# AP4BP-module-breakout_rev_a-v7.net
KiCad netlist of a schematic drawn in EAGLE
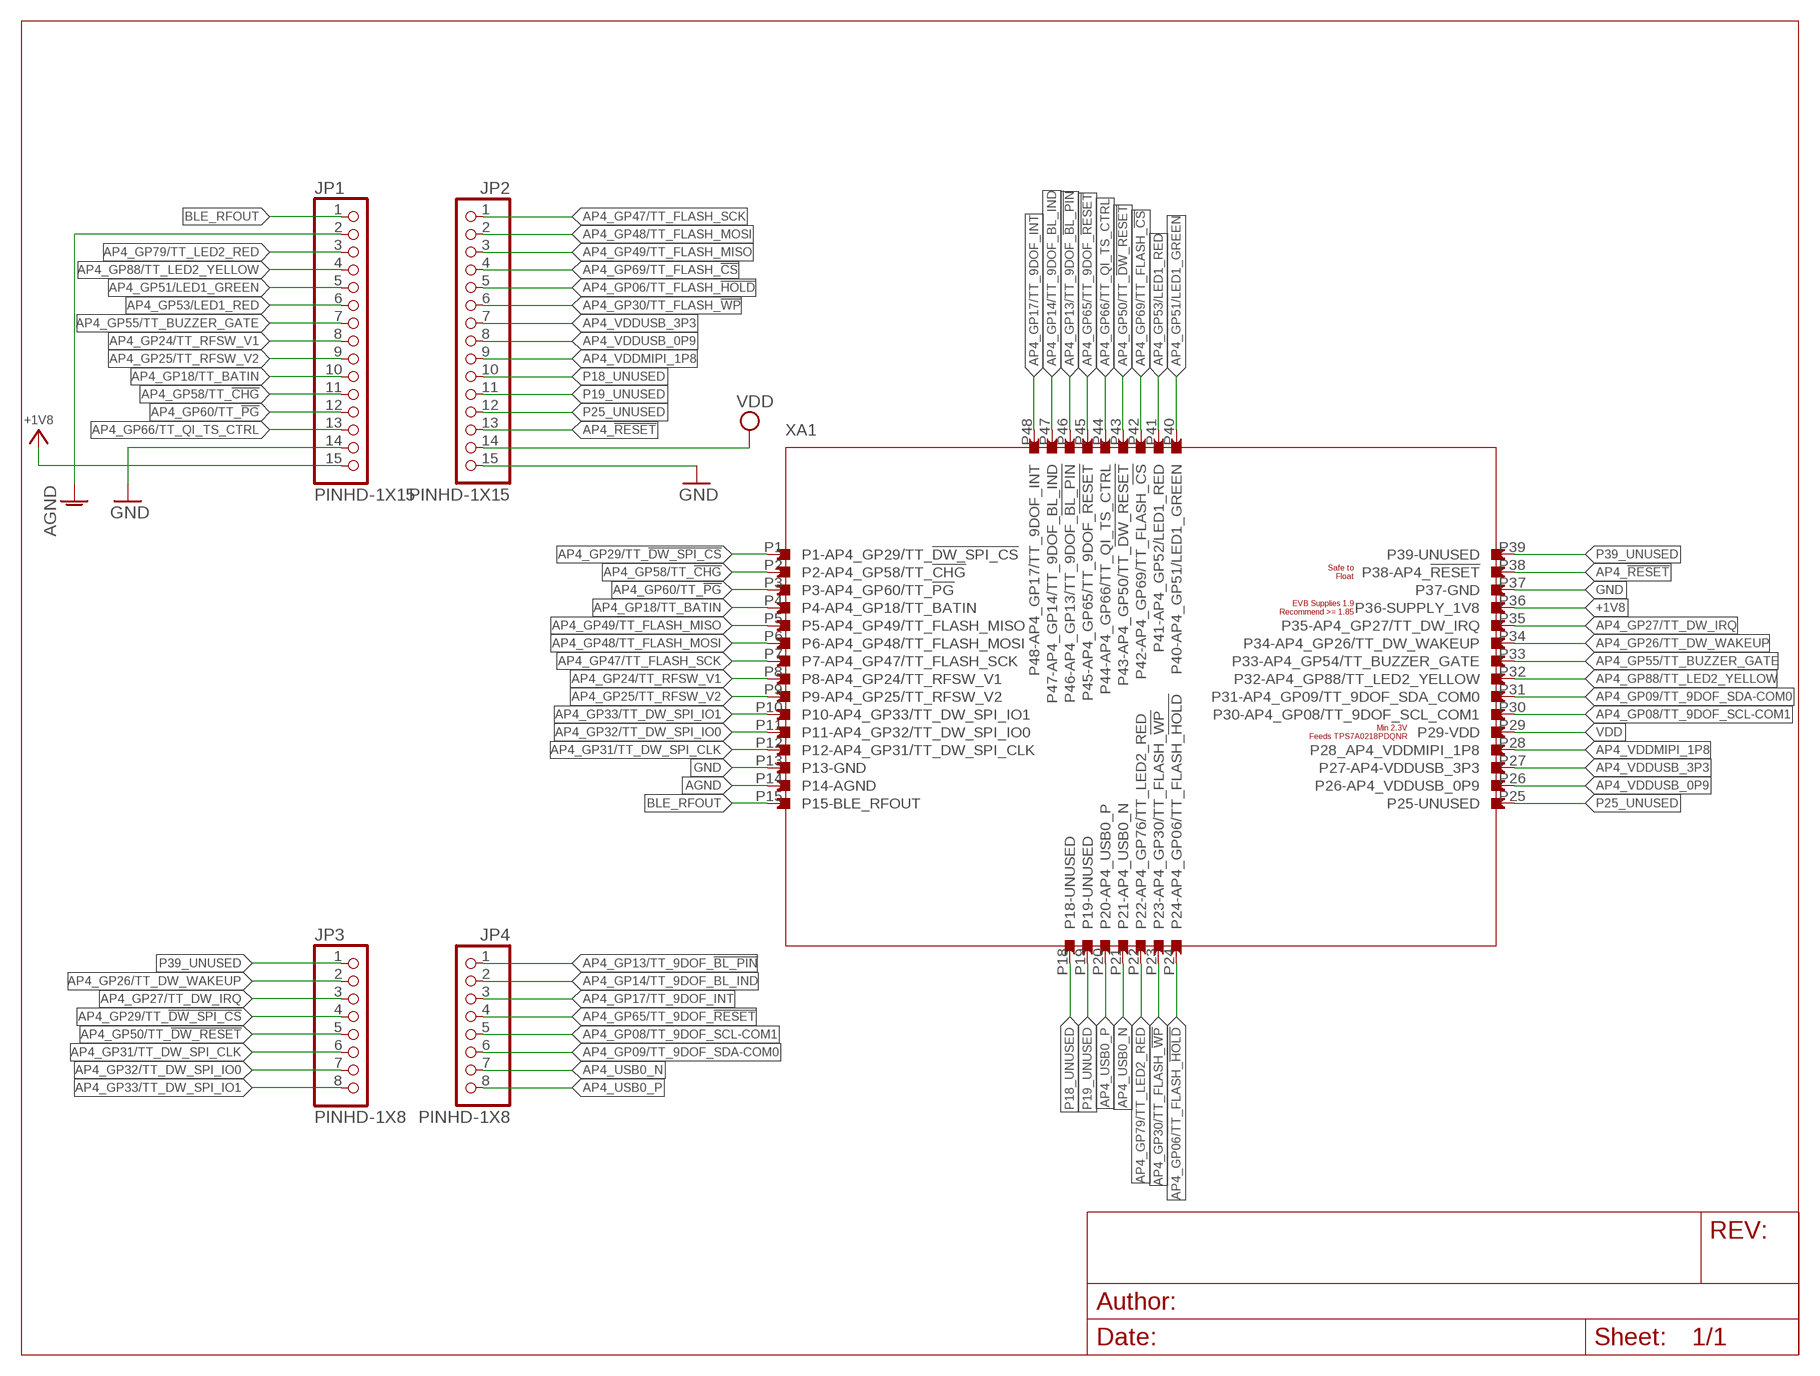
[diagram p0: schematic, sheet 1]

(export (version "E")
  (design (tool "Eeschema 10.0.6"))
  (components
    (comp (ref "JP1")
      (value "PINHD-1X15")
      (footprint "eagle-import:1X15")
      (fields (field (name "MANUFACTURER") "Generic"))
      (libsource (lib "eagle-import") (part "Connector_16378166_PINHD-1X15"))
    )
    (comp (ref "JP2")
      (value "PINHD-1X15")
      (footprint "eagle-import:1X15")
      (libsource (lib "eagle-import") (part "PINHD-1X15"))
    )
    (comp (ref "JP3")
      (value "PINHD-1X8")
      (footprint "eagle-import:1X08")
      (libsource (lib "eagle-import") (part "PINHD-1X8"))
    )
    (comp (ref "JP4")
      (value "PINHD-1X8")
      (footprint "eagle-import:1X08")
      (libsource (lib "eagle-import") (part "PINHD-1X8"))
    )
    (comp (ref "XA1")
      (value "APOLLO4_BLUEPLUS_MODULE")
      (footprint "eagle-import:APOLLO4_BLUEPLUS_MODULE")
      (libsource (lib "eagle-import") (part "APOLLO4_BLUEPLUS_MODULE"))
    )
  )
  (nets
    (net (code "1") (name "+1V8") (class "Default")
      (node (ref "JP1") (pin "15") (pinfunction "15_15") (pintype "passive"))
      (node (ref "XA1") (pin "P36") (pinfunction "P36-SUPPLY_1V8_P36") (pintype "bidirectional"))
    )
    (net (code "2") (name "/AP4_GP06{slash}TT_FLASH_~{HOLD}") (class "Default")
      (node (ref "JP2") (pin "5") (pinfunction "5_5") (pintype "passive"))
      (node (ref "XA1") (pin "P24") (pinfunction "P24-AP4_GP06/TT_FLASH_~{HOLD}_P24") (pintype "bidirectional"))
    )
    (net (code "3") (name "/AP4_GP13{slash}TT_9DOF_~{BL_PIN}") (class "Default")
      (node (ref "JP4") (pin "1") (pinfunction "1_1") (pintype "passive"))
      (node (ref "XA1") (pin "P46") (pinfunction "P46-AP4_GP13/TT_9DOF_~{BL_PIN}_P46") (pintype "bidirectional"))
    )
    (net (code "4") (name "/AP4_GP29{slash}TT_~{DW_SPI_CS}") (class "Default")
      (node (ref "JP3") (pin "4") (pinfunction "4_4") (pintype "passive"))
      (node (ref "XA1") (pin "P1") (pinfunction "P1-AP4_GP29/TT_~{DW_SPI_CS}_P1") (pintype "bidirectional"))
    )
    (net (code "5") (name "/AP4_GP30{slash}TT_FLASH_~{WP}") (class "Default")
      (node (ref "JP2") (pin "6") (pinfunction "6_6") (pintype "passive"))
      (node (ref "XA1") (pin "P23") (pinfunction "P23-AP4_GP30/TT_FLASH_~{WP}_P23") (pintype "bidirectional"))
    )
    (net (code "6") (name "/AP4_GP50{slash}TT_~{DW_RESET}") (class "Default")
      (node (ref "JP3") (pin "5") (pinfunction "5_5") (pintype "passive"))
      (node (ref "XA1") (pin "P43") (pinfunction "P43-AP4_GP50/TT_~{DW_RESET}_P43") (pintype "bidirectional"))
    )
    (net (code "7") (name "/AP4_GP58{slash}TT_~{CHG}") (class "Default")
      (node (ref "JP1") (pin "11") (pinfunction "11_11") (pintype "passive"))
      (node (ref "XA1") (pin "P2") (pinfunction "P2-AP4_GP58/TT_~{CHG}_P2") (pintype "bidirectional"))
    )
    (net (code "8") (name "/AP4_GP60{slash}TT_~{PG}") (class "Default")
      (node (ref "JP1") (pin "12") (pinfunction "12_12") (pintype "passive"))
      (node (ref "XA1") (pin "P3") (pinfunction "P3-AP4_GP60/TT_~{PG}_P3") (pintype "bidirectional"))
    )
    (net (code "9") (name "/AP4_GP65{slash}TT_9DOF_~{RESET}") (class "Default")
      (node (ref "JP4") (pin "4") (pinfunction "4_4") (pintype "passive"))
      (node (ref "XA1") (pin "P45") (pinfunction "P45-AP4_GP65/TT_9DOF_~{RESET}_P45") (pintype "bidirectional"))
    )
    (net (code "10") (name "/AP4_GP69{slash}TT_FLASH_~{CS}") (class "Default")
      (node (ref "JP2") (pin "4") (pinfunction "4_4") (pintype "passive"))
      (node (ref "XA1") (pin "P42") (pinfunction "P42-AP4_GP69/TT_FLASH_~{CS}_P42") (pintype "bidirectional"))
    )
    (net (code "11") (name "/AP4_~{RESET}") (class "Default")
      (node (ref "JP2") (pin "13") (pinfunction "13_13") (pintype "passive"))
      (node (ref "XA1") (pin "P38") (pinfunction "P38-AP4_~{RESET}_P38") (pintype "bidirectional"))
    )
    (net (code "12") (name "AGND") (class "Default")
      (node (ref "JP1") (pin "2") (pinfunction "2_2") (pintype "passive"))
      (node (ref "XA1") (pin "P14") (pinfunction "P14-AGND_P14") (pintype "bidirectional"))
    )
    (net (code "13") (name "AP4_GP08{slash}TT_9DOF_SCL-COM1") (class "Default")
      (node (ref "JP4") (pin "5") (pinfunction "5_5") (pintype "passive"))
      (node (ref "XA1") (pin "P30") (pinfunction "P30-AP4_GP08/TT_9DOF_SCL_COM1_P30") (pintype "bidirectional"))
    )
    (net (code "14") (name "AP4_GP09{slash}TT_9DOF_SDA-COM0") (class "Default")
      (node (ref "JP4") (pin "6") (pinfunction "6_6") (pintype "passive"))
      (node (ref "XA1") (pin "P31") (pinfunction "P31-AP4_GP09/TT_9DOF_SDA_COM0_P31") (pintype "bidirectional"))
    )
    (net (code "15") (name "AP4_GP14{slash}TT_9DOF_BL_IND") (class "Default")
      (node (ref "JP4") (pin "2") (pinfunction "2_2") (pintype "passive"))
      (node (ref "XA1") (pin "P47") (pinfunction "P47-AP4_GP14/TT_9DOF_BL_IND_P47") (pintype "bidirectional"))
    )
    (net (code "16") (name "AP4_GP17{slash}TT_9DOF_INT") (class "Default")
      (node (ref "JP4") (pin "3") (pinfunction "3_3") (pintype "passive"))
      (node (ref "XA1") (pin "P48") (pinfunction "P48-AP4_GP17/TT_9DOF_INT_P48") (pintype "bidirectional"))
    )
    (net (code "17") (name "AP4_GP18{slash}TT_BATIN") (class "Default")
      (node (ref "JP1") (pin "10") (pinfunction "10_10") (pintype "passive"))
      (node (ref "XA1") (pin "P4") (pinfunction "P4-AP4_GP18/TT_BATIN_P4") (pintype "bidirectional"))
    )
    (net (code "18") (name "AP4_GP24{slash}TT_RFSW_V1") (class "Default")
      (node (ref "JP1") (pin "8") (pinfunction "8_8") (pintype "passive"))
      (node (ref "XA1") (pin "P8") (pinfunction "P8-AP4_GP24/TT_RFSW_V1_P8") (pintype "bidirectional"))
    )
    (net (code "19") (name "AP4_GP25{slash}TT_RFSW_V2") (class "Default")
      (node (ref "JP1") (pin "9") (pinfunction "9_9") (pintype "passive"))
      (node (ref "XA1") (pin "P9") (pinfunction "P9-AP4_GP25/TT_RFSW_V2_P9") (pintype "bidirectional"))
    )
    (net (code "20") (name "AP4_GP26{slash}TT_DW_WAKEUP") (class "Default")
      (node (ref "JP3") (pin "2") (pinfunction "2_2") (pintype "passive"))
      (node (ref "XA1") (pin "P34") (pinfunction "P34-AP4_GP26/TT_DW_WAKEUP_P34") (pintype "bidirectional"))
    )
    (net (code "21") (name "AP4_GP27{slash}TT_DW_IRQ") (class "Default")
      (node (ref "JP3") (pin "3") (pinfunction "3_3") (pintype "passive"))
      (node (ref "XA1") (pin "P35") (pinfunction "P35-AP4_GP27/TT_DW_IRQ_P35") (pintype "bidirectional"))
    )
    (net (code "22") (name "AP4_GP31{slash}TT_DW_SPI_CLK") (class "Default")
      (node (ref "JP3") (pin "6") (pinfunction "6_6") (pintype "passive"))
      (node (ref "XA1") (pin "P12") (pinfunction "P12-AP4_GP31/TT_DW_SPI_CLK_P12") (pintype "bidirectional"))
    )
    (net (code "23") (name "AP4_GP32{slash}TT_DW_SPI_IO0") (class "Default")
      (node (ref "JP3") (pin "7") (pinfunction "7_7") (pintype "passive"))
      (node (ref "XA1") (pin "P11") (pinfunction "P11-AP4_GP32/TT_DW_SPI_IO0_P11") (pintype "bidirectional"))
    )
    (net (code "24") (name "AP4_GP33{slash}TT_DW_SPI_IO1") (class "Default")
      (node (ref "JP3") (pin "8") (pinfunction "8_8") (pintype "passive"))
      (node (ref "XA1") (pin "P10") (pinfunction "P10-AP4_GP33/TT_DW_SPI_IO1_P10") (pintype "bidirectional"))
    )
    (net (code "25") (name "AP4_GP47{slash}TT_FLASH_SCK") (class "Default")
      (node (ref "JP2") (pin "1") (pinfunction "1_1") (pintype "passive"))
      (node (ref "XA1") (pin "P7") (pinfunction "P7-AP4_GP47/TT_FLASH_SCK_P7") (pintype "bidirectional"))
    )
    (net (code "26") (name "AP4_GP48{slash}TT_FLASH_MOSI") (class "Default")
      (node (ref "JP2") (pin "2") (pinfunction "2_2") (pintype "passive"))
      (node (ref "XA1") (pin "P6") (pinfunction "P6-AP4_GP48/TT_FLASH_MOSI_P6") (pintype "bidirectional"))
    )
    (net (code "27") (name "AP4_GP49{slash}TT_FLASH_MISO") (class "Default")
      (node (ref "JP2") (pin "3") (pinfunction "3_3") (pintype "passive"))
      (node (ref "XA1") (pin "P5") (pinfunction "P5-AP4_GP49/TT_FLASH_MISO_P5") (pintype "bidirectional"))
    )
    (net (code "28") (name "AP4_GP51{slash}LED1_GREEN") (class "Default")
      (node (ref "JP1") (pin "5") (pinfunction "5_5") (pintype "passive"))
      (node (ref "XA1") (pin "P40") (pinfunction "P40-AP4_GP51/LED1_GREEN_P40") (pintype "bidirectional"))
    )
    (net (code "29") (name "AP4_GP53{slash}LED1_RED") (class "Default")
      (node (ref "JP1") (pin "6") (pinfunction "6_6") (pintype "passive"))
      (node (ref "XA1") (pin "P41") (pinfunction "P41-AP4_GP52/LED1_RED_P41") (pintype "bidirectional"))
    )
    (net (code "30") (name "AP4_GP55{slash}TT_BUZZER_GATE") (class "Default")
      (node (ref "JP1") (pin "7") (pinfunction "7_7") (pintype "passive"))
      (node (ref "XA1") (pin "P33") (pinfunction "P33-AP4_GP54/TT_BUZZER_GATE_P33") (pintype "bidirectional"))
    )
    (net (code "31") (name "AP4_GP66{slash}TT_QI_TS_CTRL") (class "Default")
      (node (ref "JP1") (pin "13") (pinfunction "13_13") (pintype "passive"))
      (node (ref "XA1") (pin "P44") (pinfunction "P44-AP4_GP66/TT_QI_TS_CTRL_P44") (pintype "bidirectional"))
    )
    (net (code "32") (name "AP4_GP79{slash}TT_LED2_RED") (class "Default")
      (node (ref "JP1") (pin "3") (pinfunction "3_3") (pintype "passive"))
      (node (ref "XA1") (pin "P22") (pinfunction "P22-AP4_GP76/TT_LED2_RED_P22") (pintype "bidirectional"))
    )
    (net (code "33") (name "AP4_GP88{slash}TT_LED2_YELLOW") (class "Default")
      (node (ref "JP1") (pin "4") (pinfunction "4_4") (pintype "passive"))
      (node (ref "XA1") (pin "P32") (pinfunction "P32-AP4_GP88/TT_LED2_YELLOW_P32") (pintype "bidirectional"))
    )
    (net (code "34") (name "AP4_USB0_N") (class "Default")
      (node (ref "JP4") (pin "7") (pinfunction "7_7") (pintype "passive"))
      (node (ref "XA1") (pin "P21") (pinfunction "P21-AP4_USB0_N_P21") (pintype "bidirectional"))
    )
    (net (code "35") (name "AP4_USB0_P") (class "Default")
      (node (ref "JP4") (pin "8") (pinfunction "8_8") (pintype "passive"))
      (node (ref "XA1") (pin "P20") (pinfunction "P20-AP4_USB0_P_P20") (pintype "bidirectional"))
    )
    (net (code "36") (name "AP4_VDDMIPI_1P8") (class "Default")
      (node (ref "JP2") (pin "9") (pinfunction "9_9") (pintype "passive"))
      (node (ref "XA1") (pin "P28") (pinfunction "P28_AP4_VDDMIPI_1P8_P28") (pintype "bidirectional"))
    )
    (net (code "37") (name "AP4_VDDUSB_0P9") (class "Default")
      (node (ref "JP2") (pin "8") (pinfunction "8_8") (pintype "passive"))
      (node (ref "XA1") (pin "P26") (pinfunction "P26-AP4_VDDUSB_0P9_P26") (pintype "bidirectional"))
    )
    (net (code "38") (name "AP4_VDDUSB_3P3") (class "Default")
      (node (ref "JP2") (pin "7") (pinfunction "7_7") (pintype "passive"))
      (node (ref "XA1") (pin "P27") (pinfunction "P27-AP4-VDDUSB_3P3_P27") (pintype "bidirectional"))
    )
    (net (code "39") (name "BLE_RFOUT") (class "Default")
      (node (ref "JP1") (pin "1") (pinfunction "1_1") (pintype "passive"))
      (node (ref "XA1") (pin "P15") (pinfunction "P15-BLE_RFOUT_P15") (pintype "bidirectional"))
    )
    (net (code "40") (name "GND") (class "Default")
      (node (ref "JP1") (pin "14") (pinfunction "14_14") (pintype "passive"))
      (node (ref "JP2") (pin "15") (pinfunction "15_15") (pintype "passive"))
      (node (ref "XA1") (pin "P13") (pinfunction "P13-GND_P13") (pintype "bidirectional"))
      (node (ref "XA1") (pin "P37") (pinfunction "P37-GND_P37") (pintype "bidirectional"))
    )
    (net (code "41") (name "P18_UNUSED") (class "Default")
      (node (ref "JP2") (pin "10") (pinfunction "10_10") (pintype "passive"))
      (node (ref "XA1") (pin "P18") (pinfunction "P18-UNUSED_P18") (pintype "bidirectional"))
    )
    (net (code "42") (name "P19_UNUSED") (class "Default")
      (node (ref "JP2") (pin "11") (pinfunction "11_11") (pintype "passive"))
      (node (ref "XA1") (pin "P19") (pinfunction "P19-UNUSED_P19") (pintype "bidirectional"))
    )
    (net (code "43") (name "P25_UNUSED") (class "Default")
      (node (ref "JP2") (pin "12") (pinfunction "12_12") (pintype "passive"))
      (node (ref "XA1") (pin "P25") (pinfunction "P25-UNUSED_P25") (pintype "bidirectional"))
    )
    (net (code "44") (name "P39_UNUSED") (class "Default")
      (node (ref "JP3") (pin "1") (pinfunction "1_1") (pintype "passive"))
      (node (ref "XA1") (pin "P39") (pinfunction "P39-UNUSED_P39") (pintype "bidirectional"))
    )
    (net (code "45") (name "VDD") (class "Default")
      (node (ref "JP2") (pin "14") (pinfunction "14_14") (pintype "passive"))
      (node (ref "XA1") (pin "P29") (pinfunction "P29-VDD_P29") (pintype "bidirectional"))
    )
  )
)
